# source_eagle.net
KiCad netlist of a schematic drawn in EAGLE
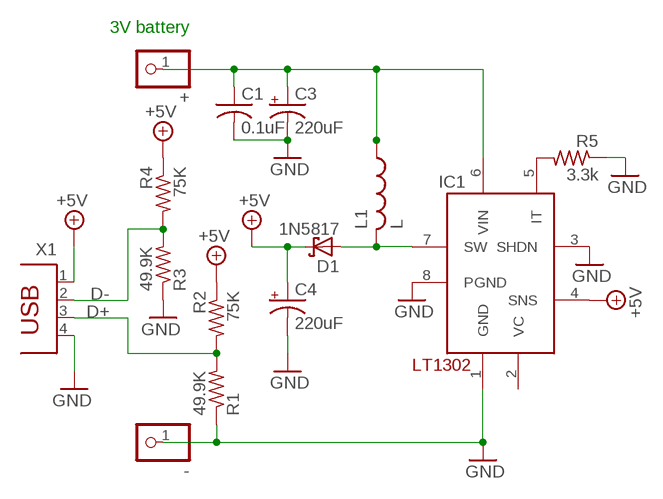
[diagram p0: schematic, sheet 1]

(export (version "E")
  (design (tool "Eeschema 10.0.6"))
  (components
    (comp (ref "+")
      (value "PINHD-1X1")
      (footprint "eagle-import:1X01")
      (libsource (lib "eagle-import") (part "PINHD-1X1"))
    )
    (comp (ref "-")
      (value "PINHD-1X1")
      (footprint "eagle-import:1X01")
      (libsource (lib "eagle-import") (part "PINHD-1X1"))
    )
    (comp (ref "C1")
      (value "0.1uF")
      (footprint "eagle-import:C025-025X050")
      (libsource (lib "eagle-import") (part "C-US025-025X050"))
    )
    (comp (ref "C3")
      (value "220uF")
      (footprint "eagle-import:E2,5-5")
      (libsource (lib "eagle-import") (part "CPOL-USE2.5-5"))
    )
    (comp (ref "C4")
      (value "220uF")
      (footprint "eagle-import:E2,5-5")
      (libsource (lib "eagle-import") (part "CPOL-USE2.5-5"))
    )
    (comp (ref "D1")
      (value "1N5817")
      (footprint "eagle-import:DO41-7")
      (libsource (lib "eagle-import") (part "SCHOTTKY-DIODEDO41-7"))
    )
    (comp (ref "IC1")
      (value "LT1302")
      (footprint "eagle-import:DIL08")
      (libsource (lib "eagle-import") (part "LT1302"))
    )
    (comp (ref "L1") (value "L") (footprint "eagle-import:6000") (libsource (lib "eagle-import") (part "L")))
    (comp (ref "R1")
      (value "49.9K")
      (footprint "eagle-import:0204_5")
      (libsource (lib "eagle-import") (part "R-US_0204/5"))
    )
    (comp (ref "R2")
      (value "75K")
      (footprint "eagle-import:0204_5")
      (libsource (lib "eagle-import") (part "R-US_0204/5"))
    )
    (comp (ref "R3")
      (value "49.9K")
      (footprint "eagle-import:0204_5")
      (libsource (lib "eagle-import") (part "R-US_0204/5"))
    )
    (comp (ref "R4")
      (value "75K")
      (footprint "eagle-import:0204_5")
      (libsource (lib "eagle-import") (part "R-US_0204/5"))
    )
    (comp (ref "R5")
      (value "3.3k")
      (footprint "eagle-import:0204_5")
      (libsource (lib "eagle-import") (part "R-US_0204/5"))
    )
    (comp (ref "X1")
      (value "PN87520")
      (footprint "eagle-import:PN87520")
      (libsource (lib "eagle-import") (part "PN87520"))
    )
  )
  (nets
    (net (code "1") (name "+5V") (class "Default")
      (node (ref "C4") (pin "+") (pinfunction "+_+") (pintype "passive"))
      (node (ref "D1") (pin "C") (pinfunction "C_C") (pintype "passive"))
      (node (ref "IC1") (pin "4") (pinfunction "SNS_4") (pintype "passive"))
      (node (ref "R2") (pin "1") (pinfunction "1_1") (pintype "passive"))
      (node (ref "R4") (pin "1") (pinfunction "1_1") (pintype "passive"))
      (node (ref "X1") (pin "1") (pinfunction "1_1") (pintype "bidirectional"))
    )
    (net (code "2") (name "/D+") (class "Default")
      (node (ref "R1") (pin "2") (pinfunction "2_2") (pintype "passive"))
      (node (ref "R2") (pin "2") (pinfunction "2_2") (pintype "passive"))
      (node (ref "X1") (pin "3") (pinfunction "3_3") (pintype "bidirectional"))
    )
    (net (code "3") (name "/D-") (class "Default")
      (node (ref "R3") (pin "2") (pinfunction "2_2") (pintype "passive"))
      (node (ref "R4") (pin "2") (pinfunction "2_2") (pintype "passive"))
      (node (ref "X1") (pin "2") (pinfunction "2_2") (pintype "bidirectional"))
    )
    (net (code "4") (name "GND") (class "Default")
      (node (ref "-") (pin "1") (pinfunction "1_1") (pintype "passive"))
      (node (ref "C1") (pin "2") (pinfunction "2_2") (pintype "passive"))
      (node (ref "C3") (pin "-") (pinfunction "-_-") (pintype "passive"))
      (node (ref "C4") (pin "-") (pinfunction "-_-") (pintype "passive"))
      (node (ref "IC1") (pin "1") (pinfunction "GND_1") (pintype "input"))
      (node (ref "IC1") (pin "3") (pinfunction "SHDN_3") (pintype "input"))
      (node (ref "IC1") (pin "8") (pinfunction "PGND_8") (pintype "input"))
      (node (ref "R1") (pin "1") (pinfunction "1_1") (pintype "passive"))
      (node (ref "R3") (pin "1") (pinfunction "1_1") (pintype "passive"))
      (node (ref "R5") (pin "1") (pinfunction "1_1") (pintype "passive"))
      (node (ref "X1") (pin "4") (pinfunction "4_4") (pintype "bidirectional"))
    )
    (net (code "5") (name "Net-(IC1-IT)") (class "Default")
      (node (ref "IC1") (pin "5") (pinfunction "IT_5") (pintype "input"))
      (node (ref "R5") (pin "2") (pinfunction "2_2") (pintype "passive"))
    )
    (net (code "6") (name "Net-(IC1-SW)") (class "Default")
      (node (ref "D1") (pin "A") (pinfunction "A_A") (pintype "passive"))
      (node (ref "IC1") (pin "7") (pinfunction "SW_7") (pintype "input"))
      (node (ref "L1") (pin "2") (pinfunction "2_2") (pintype "passive"))
    )
    (net (code "7") (name "Net-(IC1-VIN)") (class "Default")
      (node (ref "+") (pin "1") (pinfunction "1_1") (pintype "passive"))
      (node (ref "C1") (pin "1") (pinfunction "1_1") (pintype "passive"))
      (node (ref "C3") (pin "+") (pinfunction "+_+") (pintype "passive"))
      (node (ref "IC1") (pin "6") (pinfunction "VIN_6") (pintype "input"))
      (node (ref "L1") (pin "1") (pinfunction "1_1") (pintype "passive"))
    )
    (net (code "8") (name "unconnected-(IC1-VC-Pad2)") (class "Default")
      (node (ref "IC1") (pin "2") (pinfunction "VC_2") (pintype "passive"))
    )
  )
)
